# Practicum_Schematic.net
KiCad netlist of a schematic drawn in EAGLE
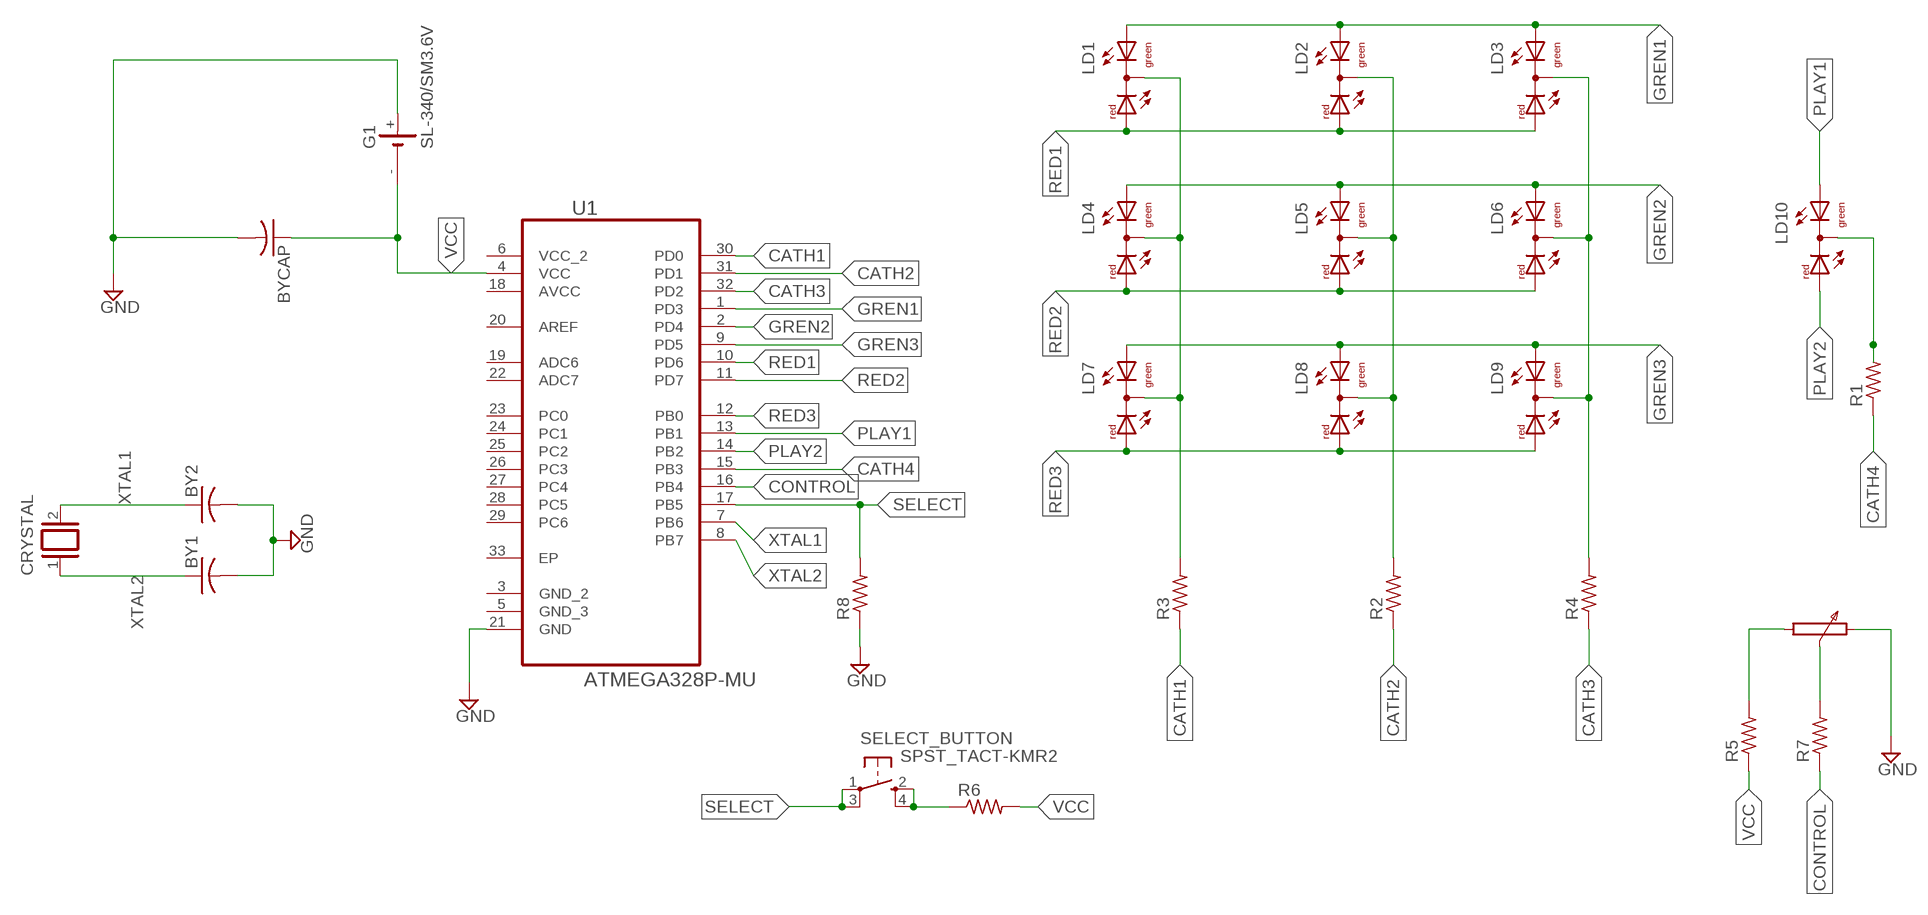
[diagram p0: schematic, sheet 1]

(export (version "E")
  (design (tool "Eeschema 10.0.6"))
  (components
    (comp (ref "BY1")
      (value "C-USC0805")
      (footprint "eagle-import:C0805")
      (libsource (lib "eagle-import") (part "C-USC0805"))
    )
    (comp (ref "BY2")
      (value "C-USC0805")
      (footprint "eagle-import:C0805")
      (libsource (lib "eagle-import") (part "C-USC0805"))
    )
    (comp (ref "BYCAP")
      (value "C-USC0805")
      (footprint "eagle-import:C0805")
      (libsource (lib "eagle-import") (part "C-USC0805"))
    )
    (comp (ref "CRYSTAL")
      (value "XTAL/S")
      (footprint "eagle-import:QS")
      (libsource (lib "eagle-import") (part "XTAL/S"))
    )
    (comp (ref "G1")
      (value "SL-340/SM3.6V")
      (footprint "eagle-import:SL-340_SM3.6V")
      (libsource (lib "eagle-import") (part "SL-340/SM3.6V"))
    )
    (comp (ref "LD1")
      (value "DUOLED-RG-C")
      (footprint "eagle-import:DUOLED-C-5MM")
      (libsource (lib "eagle-import") (part "DUOLED-RG-C"))
    )
    (comp (ref "LD2")
      (value "DUOLED-RG-C")
      (footprint "eagle-import:DUOLED-C-5MM")
      (libsource (lib "eagle-import") (part "DUOLED-RG-C"))
    )
    (comp (ref "LD3")
      (value "DUOLED-RG-C")
      (footprint "eagle-import:DUOLED-C-5MM")
      (libsource (lib "eagle-import") (part "DUOLED-RG-C"))
    )
    (comp (ref "LD4")
      (value "DUOLED-RG-C")
      (footprint "eagle-import:DUOLED-C-5MM")
      (libsource (lib "eagle-import") (part "DUOLED-RG-C"))
    )
    (comp (ref "LD5")
      (value "DUOLED-RG-C")
      (footprint "eagle-import:DUOLED-C-5MM")
      (libsource (lib "eagle-import") (part "DUOLED-RG-C"))
    )
    (comp (ref "LD6")
      (value "DUOLED-RG-C")
      (footprint "eagle-import:DUOLED-C-5MM")
      (libsource (lib "eagle-import") (part "DUOLED-RG-C"))
    )
    (comp (ref "LD7")
      (value "DUOLED-RG-C")
      (footprint "eagle-import:DUOLED-C-5MM")
      (libsource (lib "eagle-import") (part "DUOLED-RG-C"))
    )
    (comp (ref "LD8")
      (value "DUOLED-RG-C")
      (footprint "eagle-import:DUOLED-C-5MM")
      (libsource (lib "eagle-import") (part "DUOLED-RG-C"))
    )
    (comp (ref "LD9")
      (value "DUOLED-RG-C")
      (footprint "eagle-import:DUOLED-C-5MM")
      (libsource (lib "eagle-import") (part "DUOLED-RG-C"))
    )
    (comp (ref "LD10")
      (value "DUOLED-RG-C")
      (footprint "eagle-import:DUOLED-C-5MM")
      (libsource (lib "eagle-import") (part "DUOLED-RG-C"))
    )
    (comp (ref "R1")
      (value "R-US_M0805")
      (footprint "eagle-import:M0805")
      (libsource (lib "eagle-import") (part "R-US_M0805"))
    )
    (comp (ref "R2")
      (value "R-US_M0805")
      (footprint "eagle-import:M0805")
      (libsource (lib "eagle-import") (part "R-US_M0805"))
    )
    (comp (ref "R3")
      (value "R-US_M0805")
      (footprint "eagle-import:M0805")
      (libsource (lib "eagle-import") (part "R-US_M0805"))
    )
    (comp (ref "R4")
      (value "R-US_M0805")
      (footprint "eagle-import:M0805")
      (libsource (lib "eagle-import") (part "R-US_M0805"))
    )
    (comp (ref "R5")
      (value "R-US_M0805")
      (footprint "eagle-import:M0805")
      (libsource (lib "eagle-import") (part "R-US_M0805"))
    )
    (comp (ref "R6")
      (value "R-US_M0805")
      (footprint "eagle-import:M0805")
      (libsource (lib "eagle-import") (part "R-US_M0805"))
    )
    (comp (ref "R7")
      (value "R-US_M0805")
      (footprint "eagle-import:M0805")
      (libsource (lib "eagle-import") (part "R-US_M0805"))
    )
    (comp (ref "R8")
      (value "R-US_M0805")
      (footprint "eagle-import:M0805")
      (libsource (lib "eagle-import") (part "R-US_M0805"))
    )
    (comp (ref "SELECT_BUTTON")
      (value "SPST_TACT-KMR2")
      (footprint "eagle-import:KMR2")
      (libsource (lib "eagle-import") (part "SPST_TACT-KMR2"))
    )
    (comp (ref "U1")
      (value "ATMEGA328P-MU")
      (footprint "eagle-import:QFN50P500X500X100-33N")
      (libsource (lib "eagle-import") (part "ATMEGA328P-MU"))
    )
  )
  (nets
    (net (code "1") (name "/AVCC") (class "Default")
      (node (ref "U1") (pin "18") (pinfunction "AVCC_18") (pintype "power_in"))
    )
    (net (code "2") (name "/VCC_2") (class "Default")
      (node (ref "U1") (pin "6") (pinfunction "VCC_2_6") (pintype "power_in"))
    )
    (net (code "3") (name "CATH1") (class "Default")
      (node (ref "R3") (pin "1") (pinfunction "1_1") (pintype "passive"))
      (node (ref "U1") (pin "30") (pinfunction "PD0_30") (pintype "bidirectional"))
    )
    (net (code "4") (name "CATH2") (class "Default")
      (node (ref "R2") (pin "1") (pinfunction "1_1") (pintype "passive"))
      (node (ref "U1") (pin "31") (pinfunction "PD1_31") (pintype "bidirectional"))
    )
    (net (code "5") (name "CATH3") (class "Default")
      (node (ref "R4") (pin "1") (pinfunction "1_1") (pintype "passive"))
      (node (ref "U1") (pin "32") (pinfunction "PD2_32") (pintype "bidirectional"))
    )
    (net (code "6") (name "CATH4") (class "Default")
      (node (ref "R1") (pin "1") (pinfunction "1_1") (pintype "passive"))
      (node (ref "U1") (pin "15") (pinfunction "PB3_15") (pintype "bidirectional"))
    )
    (net (code "7") (name "CONTROL") (class "Default")
      (node (ref "R7") (pin "1") (pinfunction "1_1") (pintype "passive"))
      (node (ref "U1") (pin "16") (pinfunction "PB4_16") (pintype "bidirectional"))
    )
    (net (code "8") (name "GND") (class "Default")
      (node (ref "BY1") (pin "2") (pinfunction "2_2") (pintype "passive"))
      (node (ref "BY2") (pin "2") (pinfunction "2_2") (pintype "passive"))
      (node (ref "BYCAP") (pin "2") (pinfunction "2_2") (pintype "passive"))
      (node (ref "G1") (pin "+") (pinfunction "+_+") (pintype "passive"))
      (node (ref "R8") (pin "1") (pinfunction "1_1") (pintype "passive"))
      (node (ref "U1") (pin "21") (pinfunction "GND_21") (pintype "passive"))
    )
    (net (code "9") (name "GREN1") (class "Default")
      (node (ref "LD1") (pin "AX") (pinfunction "AG_AX") (pintype "passive"))
      (node (ref "LD2") (pin "AX") (pinfunction "AG_AX") (pintype "passive"))
      (node (ref "LD3") (pin "AX") (pinfunction "AG_AX") (pintype "passive"))
      (node (ref "U1") (pin "1") (pinfunction "PD3_1") (pintype "bidirectional"))
    )
    (net (code "10") (name "GREN2") (class "Default")
      (node (ref "LD4") (pin "AX") (pinfunction "AG_AX") (pintype "passive"))
      (node (ref "LD5") (pin "AX") (pinfunction "AG_AX") (pintype "passive"))
      (node (ref "LD6") (pin "AX") (pinfunction "AG_AX") (pintype "passive"))
      (node (ref "U1") (pin "2") (pinfunction "PD4_2") (pintype "bidirectional"))
    )
    (net (code "11") (name "GREN3") (class "Default")
      (node (ref "LD7") (pin "AX") (pinfunction "AG_AX") (pintype "passive"))
      (node (ref "LD8") (pin "AX") (pinfunction "AG_AX") (pintype "passive"))
      (node (ref "LD9") (pin "AX") (pinfunction "AG_AX") (pintype "passive"))
      (node (ref "U1") (pin "9") (pinfunction "PD5_9") (pintype "bidirectional"))
    )
    (net (code "12") (name "Net-(LD1-PadC)") (class "Default")
      (node (ref "LD1") (pin "C") (pinfunction "C_C") (pintype "passive"))
      (node (ref "LD4") (pin "C") (pinfunction "C_C") (pintype "passive"))
      (node (ref "LD7") (pin "C") (pinfunction "C_C") (pintype "passive"))
      (node (ref "R3") (pin "2") (pinfunction "2_2") (pintype "passive"))
    )
    (net (code "13") (name "Net-(LD2-PadC)") (class "Default")
      (node (ref "LD2") (pin "C") (pinfunction "C_C") (pintype "passive"))
      (node (ref "LD5") (pin "C") (pinfunction "C_C") (pintype "passive"))
      (node (ref "LD8") (pin "C") (pinfunction "C_C") (pintype "passive"))
      (node (ref "R2") (pin "2") (pinfunction "2_2") (pintype "passive"))
    )
    (net (code "14") (name "Net-(LD3-PadC)") (class "Default")
      (node (ref "LD3") (pin "C") (pinfunction "C_C") (pintype "passive"))
      (node (ref "LD6") (pin "C") (pinfunction "C_C") (pintype "passive"))
      (node (ref "LD9") (pin "C") (pinfunction "C_C") (pintype "passive"))
      (node (ref "R4") (pin "2") (pinfunction "2_2") (pintype "passive"))
    )
    (net (code "15") (name "Net-(LD10-PadC)") (class "Default")
      (node (ref "LD10") (pin "C") (pinfunction "C_C") (pintype "passive"))
      (node (ref "R1") (pin "2") (pinfunction "2_2") (pintype "passive"))
    )
    (net (code "16") (name "Net-(SELECT_BUTTON-S)") (class "Default")
      (node (ref "R6") (pin "1") (pinfunction "1_1") (pintype "passive"))
      (node (ref "SELECT_BUTTON") (pin "2") (pinfunction "S_2") (pintype "passive"))
      (node (ref "SELECT_BUTTON") (pin "4") (pinfunction "S1_4") (pintype "passive"))
    )
    (net (code "17") (name "PLAY1") (class "Default")
      (node (ref "LD10") (pin "AX") (pinfunction "AG_AX") (pintype "passive"))
      (node (ref "U1") (pin "13") (pinfunction "PB1_13") (pintype "bidirectional"))
    )
    (net (code "18") (name "PLAY2") (class "Default")
      (node (ref "LD10") (pin "AR") (pinfunction "AR_AR") (pintype "passive"))
      (node (ref "U1") (pin "14") (pinfunction "PB2_14") (pintype "bidirectional"))
    )
    (net (code "19") (name "RED1") (class "Default")
      (node (ref "LD1") (pin "AR") (pinfunction "AR_AR") (pintype "passive"))
      (node (ref "LD2") (pin "AR") (pinfunction "AR_AR") (pintype "passive"))
      (node (ref "LD3") (pin "AR") (pinfunction "AR_AR") (pintype "passive"))
      (node (ref "U1") (pin "10") (pinfunction "PD6_10") (pintype "bidirectional"))
    )
    (net (code "20") (name "RED2") (class "Default")
      (node (ref "LD4") (pin "AR") (pinfunction "AR_AR") (pintype "passive"))
      (node (ref "LD5") (pin "AR") (pinfunction "AR_AR") (pintype "passive"))
      (node (ref "LD6") (pin "AR") (pinfunction "AR_AR") (pintype "passive"))
      (node (ref "U1") (pin "11") (pinfunction "PD7_11") (pintype "bidirectional"))
    )
    (net (code "21") (name "RED3") (class "Default")
      (node (ref "LD7") (pin "AR") (pinfunction "AR_AR") (pintype "passive"))
      (node (ref "LD8") (pin "AR") (pinfunction "AR_AR") (pintype "passive"))
      (node (ref "LD9") (pin "AR") (pinfunction "AR_AR") (pintype "passive"))
      (node (ref "U1") (pin "12") (pinfunction "PB0_12") (pintype "bidirectional"))
    )
    (net (code "22") (name "SELECT") (class "Default")
      (node (ref "R8") (pin "2") (pinfunction "2_2") (pintype "passive"))
      (node (ref "SELECT_BUTTON") (pin "1") (pinfunction "P_1") (pintype "passive"))
      (node (ref "SELECT_BUTTON") (pin "3") (pinfunction "P1_3") (pintype "passive"))
      (node (ref "U1") (pin "17") (pinfunction "PB5_17") (pintype "bidirectional"))
    )
    (net (code "23") (name "VCC") (class "Default")
      (node (ref "BYCAP") (pin "1") (pinfunction "1_1") (pintype "passive"))
      (node (ref "G1") (pin "-") (pinfunction "-_-") (pintype "passive"))
      (node (ref "R5") (pin "1") (pinfunction "1_1") (pintype "passive"))
      (node (ref "R6") (pin "2") (pinfunction "2_2") (pintype "passive"))
      (node (ref "U1") (pin "4") (pinfunction "VCC_4") (pintype "power_in"))
    )
    (net (code "24") (name "XTAL1") (class "Default")
      (node (ref "BY2") (pin "1") (pinfunction "1_1") (pintype "passive"))
      (node (ref "CRYSTAL") (pin "2") (pinfunction "2_2") (pintype "passive"))
      (node (ref "U1") (pin "7") (pinfunction "PB6_7") (pintype "bidirectional"))
    )
    (net (code "25") (name "XTAL2") (class "Default")
      (node (ref "BY1") (pin "1") (pinfunction "1_1") (pintype "passive"))
      (node (ref "CRYSTAL") (pin "1") (pinfunction "1_1") (pintype "passive"))
      (node (ref "U1") (pin "8") (pinfunction "PB7_8") (pintype "bidirectional"))
    )
    (net (code "26") (name "unconnected-(G1---Pad-@1)") (class "Default")
      (node (ref "G1") (pin "-@1") (pinfunction "-_-@1") (pintype "passive"))
    )
    (net (code "27") (name "unconnected-(R5-Pad2)") (class "Default")
      (node (ref "R5") (pin "2") (pinfunction "2_2") (pintype "passive"))
    )
    (net (code "28") (name "unconnected-(R7-Pad2)") (class "Default")
      (node (ref "R7") (pin "2") (pinfunction "2_2") (pintype "passive"))
    )
    (net (code "29") (name "unconnected-(U1-ADC6-Pad19)") (class "Default")
      (node (ref "U1") (pin "19") (pinfunction "ADC6_19") (pintype "input"))
    )
    (net (code "30") (name "unconnected-(U1-ADC7-Pad22)") (class "Default")
      (node (ref "U1") (pin "22") (pinfunction "ADC7_22") (pintype "input"))
    )
    (net (code "31") (name "unconnected-(U1-AREF-Pad20)") (class "Default")
      (node (ref "U1") (pin "20") (pinfunction "AREF_20") (pintype "input"))
    )
    (net (code "32") (name "unconnected-(U1-EP-Pad33)") (class "Default")
      (node (ref "U1") (pin "33") (pinfunction "EP_33") (pintype "passive"))
    )
    (net (code "33") (name "unconnected-(U1-GND_2-Pad3)") (class "Default")
      (node (ref "U1") (pin "3") (pinfunction "GND_2_3") (pintype "passive"))
    )
    (net (code "34") (name "unconnected-(U1-GND_3-Pad5)") (class "Default")
      (node (ref "U1") (pin "5") (pinfunction "GND_3_5") (pintype "passive"))
    )
    (net (code "35") (name "unconnected-(U1-PC0-Pad23)") (class "Default")
      (node (ref "U1") (pin "23") (pinfunction "PC0_23") (pintype "bidirectional"))
    )
    (net (code "36") (name "unconnected-(U1-PC1-Pad24)") (class "Default")
      (node (ref "U1") (pin "24") (pinfunction "PC1_24") (pintype "bidirectional"))
    )
    (net (code "37") (name "unconnected-(U1-PC2-Pad25)") (class "Default")
      (node (ref "U1") (pin "25") (pinfunction "PC2_25") (pintype "bidirectional"))
    )
    (net (code "38") (name "unconnected-(U1-PC3-Pad26)") (class "Default")
      (node (ref "U1") (pin "26") (pinfunction "PC3_26") (pintype "bidirectional"))
    )
    (net (code "39") (name "unconnected-(U1-PC4-Pad27)") (class "Default")
      (node (ref "U1") (pin "27") (pinfunction "PC4_27") (pintype "bidirectional"))
    )
    (net (code "40") (name "unconnected-(U1-PC5-Pad28)") (class "Default")
      (node (ref "U1") (pin "28") (pinfunction "PC5_28") (pintype "bidirectional"))
    )
    (net (code "41") (name "unconnected-(U1-PC6-Pad29)") (class "Default")
      (node (ref "U1") (pin "29") (pinfunction "PC6_29") (pintype "bidirectional"))
    )
  )
)
